# NewChip.net
KiCad netlist of a schematic drawn in Altium Designer
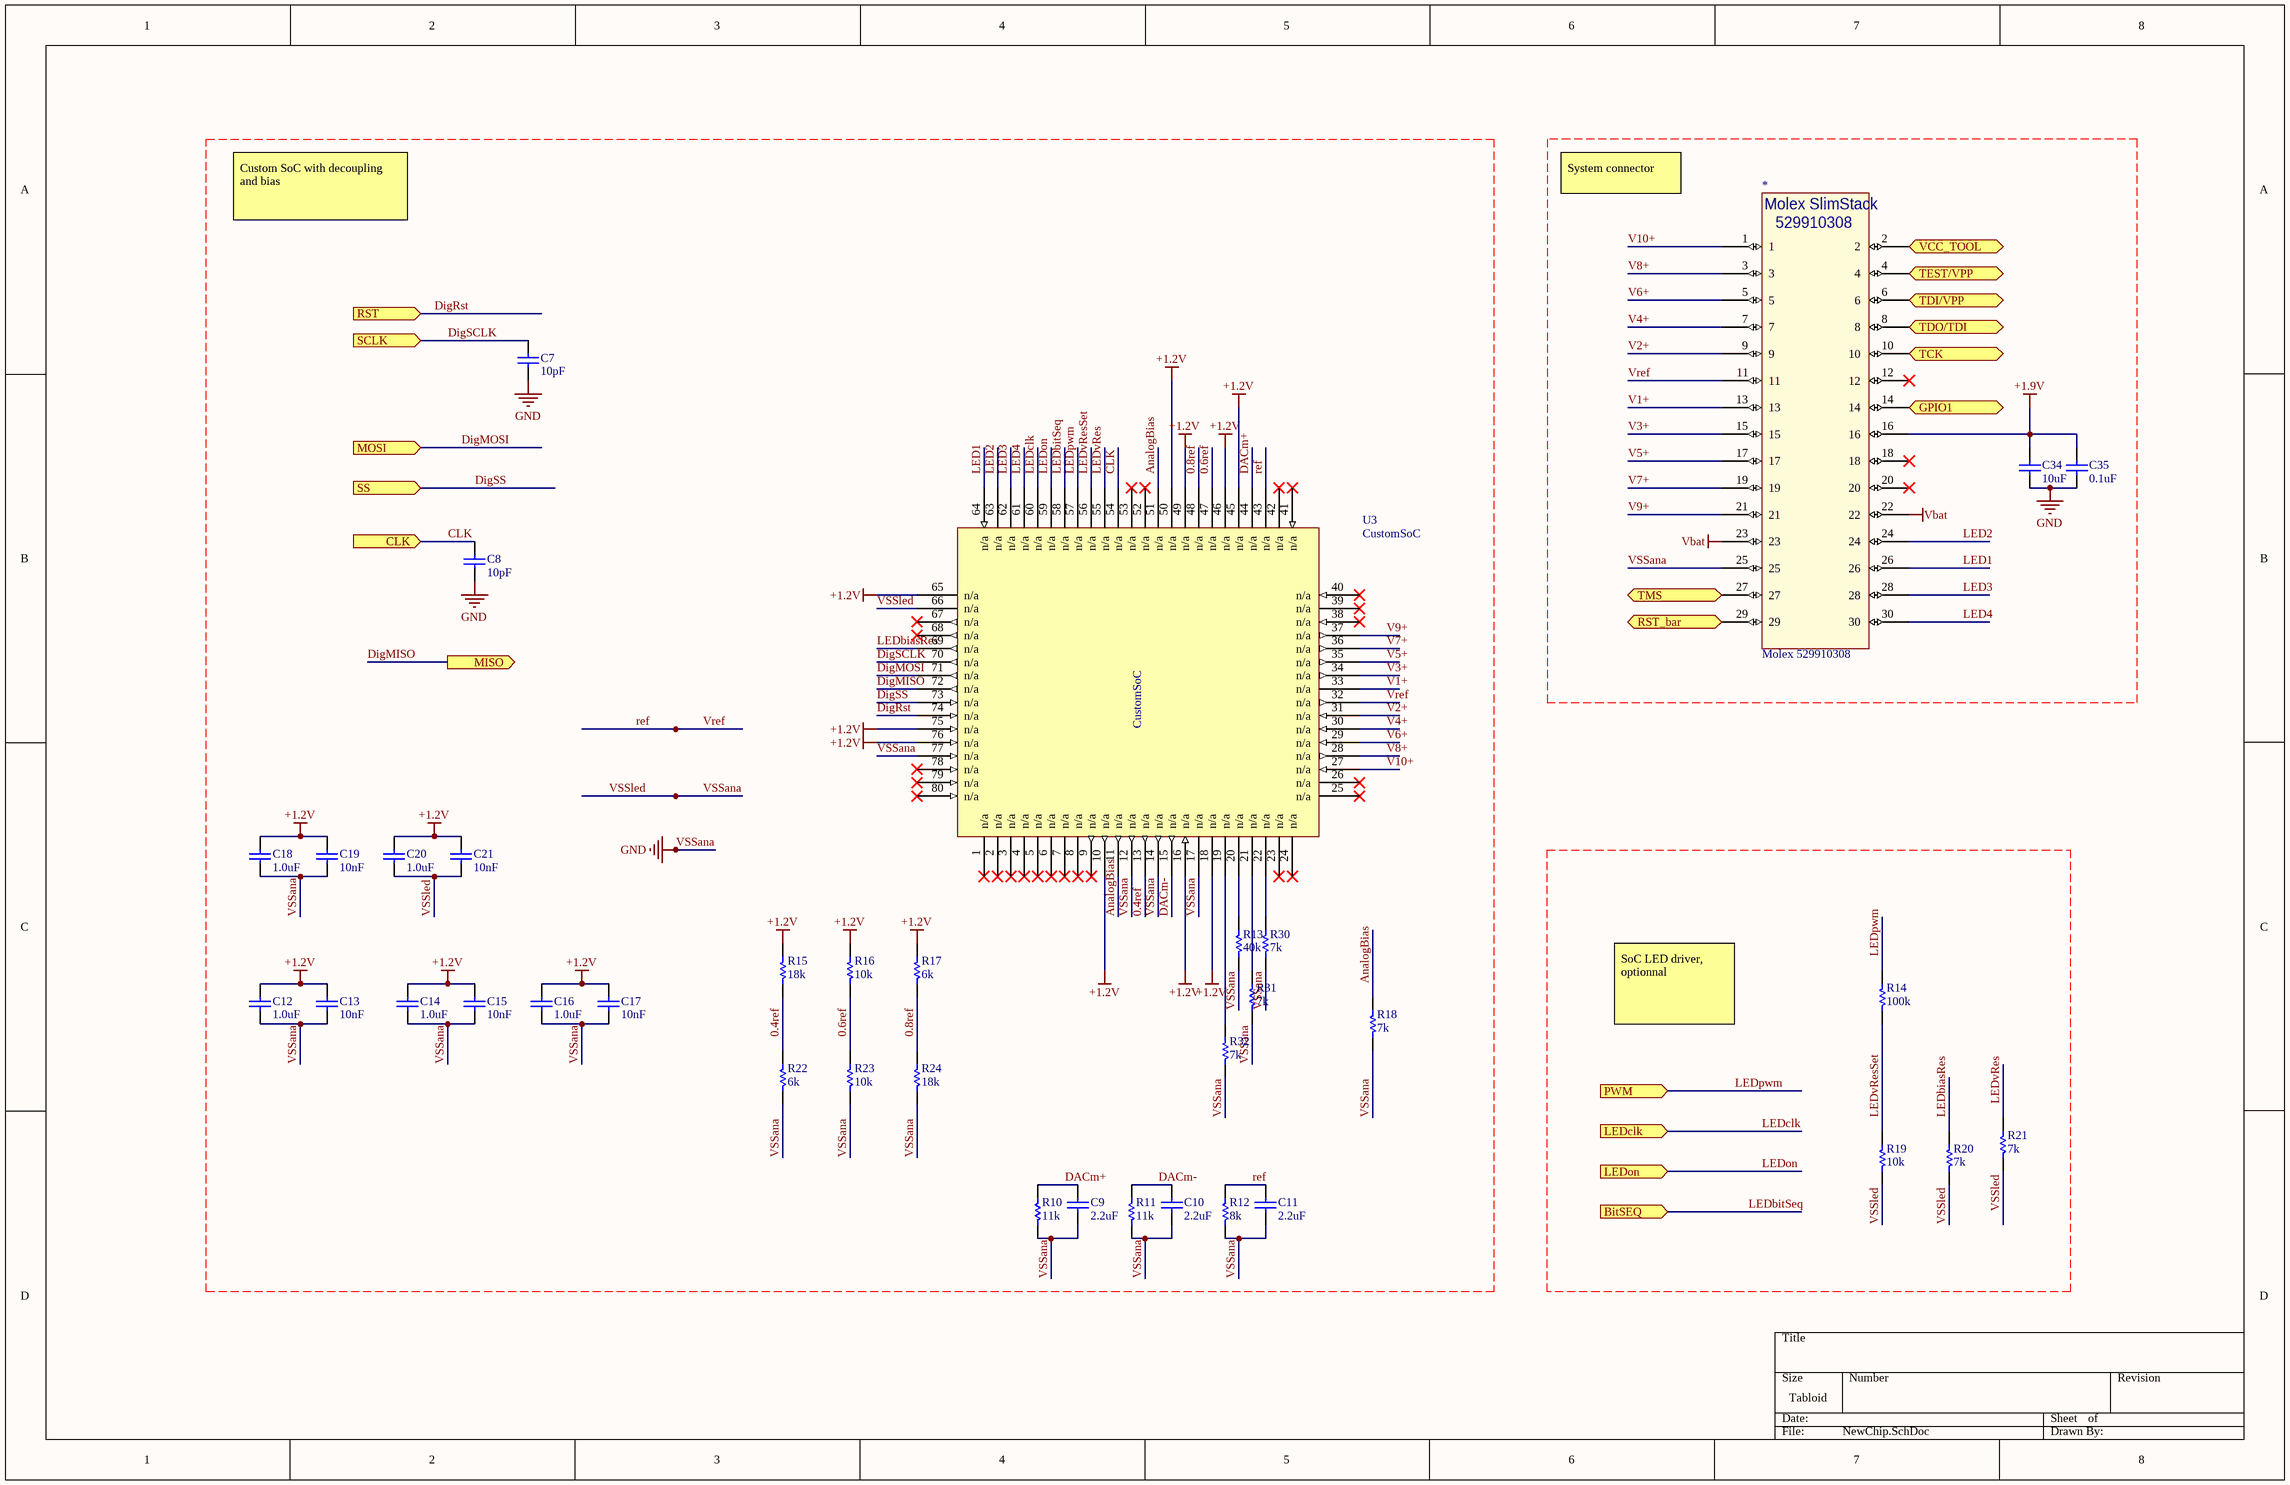
[diagram p0: NewChip.SchDoc]

(export (version "E")
  (design (tool "Eeschema 10.0.6"))
  (components
    (comp (ref "*")
      (value "Molex 529910308")
      (footprint "Molex 0529910308")
      (libsource (lib "headstage_parts") (part "Molex 529910308"))
    )
    (comp (ref "C7")
      (value "10pF")
      (footprint "0201_Custom")
      (description "Capacitor (Semiconductor SIM Model)")
      (fields (field (name "PUBLISHER") "Altium Limited"))
      (libsource (lib "Miscellaneous Devices") (part "Cap Semi"))
    )
    (comp (ref "C8")
      (value "10pF")
      (footprint "0201_Custom")
      (description "Capacitor (Semiconductor SIM Model)")
      (fields (field (name "PUBLISHER") "Altium Limited"))
      (libsource (lib "Miscellaneous Devices") (part "Cap Semi"))
    )
    (comp (ref "C9")
      (value "2.2uF")
      (footprint "0201_Custom")
      (description "Capacitor (Semiconductor SIM Model)")
      (fields (field (name "PUBLISHER") "Altium Limited"))
      (libsource (lib "Miscellaneous Devices") (part "Cap Semi"))
    )
    (comp (ref "C10")
      (value "2.2uF")
      (footprint "0201_Custom")
      (description "Capacitor (Semiconductor SIM Model)")
      (fields (field (name "PUBLISHER") "Altium Limited"))
      (libsource (lib "Miscellaneous Devices") (part "Cap Semi"))
    )
    (comp (ref "C11")
      (value "2.2uF")
      (footprint "0201_Custom")
      (description "Capacitor (Semiconductor SIM Model)")
      (fields (field (name "PUBLISHER") "Altium Limited"))
      (libsource (lib "Miscellaneous Devices") (part "Cap Semi"))
    )
    (comp (ref "C12")
      (value "1.0uF")
      (footprint "0201_Custom")
      (description "Capacitor (Semiconductor SIM Model)")
      (fields (field (name "PUBLISHER") "Altium Limited"))
      (libsource (lib "Miscellaneous Devices") (part "Cap Semi"))
    )
    (comp (ref "C13")
      (value "10nF")
      (footprint "0201_Custom")
      (description "Capacitor (Semiconductor SIM Model)")
      (fields (field (name "PUBLISHER") "Altium Limited"))
      (libsource (lib "Miscellaneous Devices") (part "Cap Semi"))
    )
    (comp (ref "C14")
      (value "1.0uF")
      (footprint "0201_Custom")
      (description "Capacitor (Semiconductor SIM Model)")
      (fields (field (name "PUBLISHER") "Altium Limited"))
      (libsource (lib "Miscellaneous Devices") (part "Cap Semi"))
    )
    (comp (ref "C15")
      (value "10nF")
      (footprint "0201_Custom")
      (description "Capacitor (Semiconductor SIM Model)")
      (fields (field (name "PUBLISHER") "Altium Limited"))
      (libsource (lib "Miscellaneous Devices") (part "Cap Semi"))
    )
    (comp (ref "C16")
      (value "1.0uF")
      (footprint "0201_Custom")
      (description "Capacitor (Semiconductor SIM Model)")
      (fields (field (name "PUBLISHER") "Altium Limited"))
      (libsource (lib "Miscellaneous Devices") (part "Cap Semi"))
    )
    (comp (ref "C17")
      (value "10nF")
      (footprint "0201_Custom")
      (description "Capacitor (Semiconductor SIM Model)")
      (fields (field (name "PUBLISHER") "Altium Limited"))
      (libsource (lib "Miscellaneous Devices") (part "Cap Semi"))
    )
    (comp (ref "C18")
      (value "1.0uF")
      (footprint "0201_Custom")
      (description "Capacitor (Semiconductor SIM Model)")
      (fields (field (name "PUBLISHER") "Altium Limited"))
      (libsource (lib "Miscellaneous Devices") (part "Cap Semi"))
    )
    (comp (ref "C19")
      (value "10nF")
      (footprint "0201_Custom")
      (description "Capacitor (Semiconductor SIM Model)")
      (fields (field (name "PUBLISHER") "Altium Limited"))
      (libsource (lib "Miscellaneous Devices") (part "Cap Semi"))
    )
    (comp (ref "C20")
      (value "1.0uF")
      (footprint "0201_Custom")
      (description "Capacitor (Semiconductor SIM Model)")
      (fields (field (name "PUBLISHER") "Altium Limited"))
      (libsource (lib "Miscellaneous Devices") (part "Cap Semi"))
    )
    (comp (ref "C21")
      (value "10nF")
      (footprint "0201_Custom")
      (description "Capacitor (Semiconductor SIM Model)")
      (fields (field (name "PUBLISHER") "Altium Limited"))
      (libsource (lib "Miscellaneous Devices") (part "Cap Semi"))
    )
    (comp (ref "C34")
      (value "10uF")
      (footprint "0402")
      (description "Capacitor (Semiconductor SIM Model)")
      (fields (field (name "PUBLISHER") "Altium Limited"))
      (libsource (lib "Miscellaneous Devices") (part "Cap Semi"))
    )
    (comp (ref "C35")
      (value "0.1uF")
      (footprint "0201_Custom")
      (description "Capacitor (Semiconductor SIM Model)")
      (fields (field (name "PUBLISHER") "Altium Limited"))
      (libsource (lib "Miscellaneous Devices") (part "Cap Semi"))
    )
    (comp (ref "R10")
      (value "11k")
      (footprint "0201_Custom")
      (description "Semiconductor Resistor")
      (fields (field (name "PUBLISHER") "Altium Limited"))
      (libsource (lib "Miscellaneous Devices") (part "Res Semi"))
    )
    (comp (ref "R11")
      (value "11k")
      (footprint "0201_Custom")
      (description "Semiconductor Resistor")
      (fields (field (name "PUBLISHER") "Altium Limited"))
      (libsource (lib "Miscellaneous Devices") (part "Res Semi"))
    )
    (comp (ref "R12")
      (value "8k")
      (footprint "0201_Custom")
      (description "Semiconductor Resistor")
      (fields (field (name "PUBLISHER") "Altium Limited"))
      (libsource (lib "Miscellaneous Devices") (part "Res Semi"))
    )
    (comp (ref "R13")
      (value "40k")
      (footprint "0201_Custom")
      (description "Semiconductor Resistor")
      (fields (field (name "PUBLISHER") "Altium Limited"))
      (libsource (lib "Miscellaneous Devices") (part "Res Semi"))
    )
    (comp (ref "R14")
      (value "100k")
      (footprint "0201_Custom")
      (description "Semiconductor Resistor")
      (fields (field (name "PUBLISHER") "Altium Limited"))
      (libsource (lib "Miscellaneous Devices") (part "Res Semi"))
    )
    (comp (ref "R15")
      (value "18k")
      (footprint "0201_Custom")
      (description "Semiconductor Resistor")
      (fields (field (name "PUBLISHER") "Altium Limited"))
      (libsource (lib "Miscellaneous Devices") (part "Res Semi"))
    )
    (comp (ref "R16")
      (value "10k")
      (footprint "0201_Custom")
      (description "Semiconductor Resistor")
      (fields (field (name "PUBLISHER") "Altium Limited"))
      (libsource (lib "Miscellaneous Devices") (part "Res Semi"))
    )
    (comp (ref "R17")
      (value "6k")
      (footprint "0201_Custom")
      (description "Semiconductor Resistor")
      (fields (field (name "PUBLISHER") "Altium Limited"))
      (libsource (lib "Miscellaneous Devices") (part "Res Semi"))
    )
    (comp (ref "R18")
      (value "7k")
      (footprint "0201_Custom")
      (description "Semiconductor Resistor")
      (fields (field (name "PUBLISHER") "Altium Limited"))
      (libsource (lib "Miscellaneous Devices") (part "Res Semi"))
    )
    (comp (ref "R19")
      (value "10k")
      (footprint "0201_Custom")
      (description "Semiconductor Resistor")
      (fields (field (name "PUBLISHER") "Altium Limited"))
      (libsource (lib "Miscellaneous Devices") (part "Res Semi"))
    )
    (comp (ref "R20")
      (value "7k")
      (footprint "0201_Custom")
      (description "Semiconductor Resistor")
      (fields (field (name "PUBLISHER") "Altium Limited"))
      (libsource (lib "Miscellaneous Devices") (part "Res Semi"))
    )
    (comp (ref "R21")
      (value "7k")
      (footprint "0201_Custom")
      (description "Semiconductor Resistor")
      (fields (field (name "PUBLISHER") "Altium Limited"))
      (libsource (lib "Miscellaneous Devices") (part "Res Semi"))
    )
    (comp (ref "R22")
      (value "6k")
      (footprint "0201_Custom")
      (description "Semiconductor Resistor")
      (fields (field (name "PUBLISHER") "Altium Limited"))
      (libsource (lib "Miscellaneous Devices") (part "Res Semi"))
    )
    (comp (ref "R23")
      (value "10k")
      (footprint "0201_Custom")
      (description "Semiconductor Resistor")
      (fields (field (name "PUBLISHER") "Altium Limited"))
      (libsource (lib "Miscellaneous Devices") (part "Res Semi"))
    )
    (comp (ref "R24")
      (value "18k")
      (footprint "0201_Custom")
      (description "Semiconductor Resistor")
      (fields (field (name "PUBLISHER") "Altium Limited"))
      (libsource (lib "Miscellaneous Devices") (part "Res Semi"))
    )
    (comp (ref "R30")
      (value "7k")
      (footprint "0201_Custom")
      (description "Semiconductor Resistor")
      (fields (field (name "PUBLISHER") "Altium Limited"))
      (libsource (lib "Miscellaneous Devices") (part "Res Semi"))
    )
    (comp (ref "R31")
      (value "7k")
      (footprint "0201_Custom")
      (description "Semiconductor Resistor")
      (fields (field (name "PUBLISHER") "Altium Limited"))
      (libsource (lib "Miscellaneous Devices") (part "Res Semi"))
    )
    (comp (ref "R32")
      (value "7k")
      (footprint "0201_Custom")
      (description "Semiconductor Resistor")
      (fields (field (name "PUBLISHER") "Altium Limited"))
      (libsource (lib "Miscellaneous Devices") (part "Res Semi"))
    )
    (comp (ref "U3")
      (value "CustomSoC")
      (footprint "CustomSoC")
      (libsource (lib "CustomLib") (part "CustomSoC"))
    )
  )
  (nets
    (net (code "1") (name "+1.2V") (class "Default")
      (node (ref "C12") (pin "1") (pinfunction "1_1") (pintype "passive"))
      (node (ref "C13") (pin "1") (pinfunction "1_1") (pintype "passive"))
      (node (ref "C14") (pin "1") (pinfunction "1_1") (pintype "passive"))
      (node (ref "C15") (pin "1") (pinfunction "1_1") (pintype "passive"))
      (node (ref "C16") (pin "1") (pinfunction "1_1") (pintype "passive"))
      (node (ref "C17") (pin "1") (pinfunction "1_1") (pintype "passive"))
      (node (ref "C18") (pin "1") (pinfunction "1_1") (pintype "passive"))
      (node (ref "C19") (pin "1") (pinfunction "1_1") (pintype "passive"))
      (node (ref "C20") (pin "1") (pinfunction "1_1") (pintype "passive"))
      (node (ref "C21") (pin "1") (pinfunction "1_1") (pintype "passive"))
      (node (ref "R15") (pin "1") (pinfunction "1_1") (pintype "passive"))
      (node (ref "R16") (pin "1") (pinfunction "1_1") (pintype "passive"))
      (node (ref "R17") (pin "1") (pinfunction "1_1") (pintype "passive"))
      (node (ref "U3") (pin "10") (pinfunction "n/a_10") (pintype "output"))
      (node (ref "U3") (pin "16") (pinfunction "n/a_16") (pintype "input"))
      (node (ref "U3") (pin "18") (pinfunction "n/a_18") (pintype "passive"))
      (node (ref "U3") (pin "45") (pinfunction "n/a_45") (pintype "passive"))
      (node (ref "U3") (pin "46") (pinfunction "n/a_46") (pintype "passive"))
      (node (ref "U3") (pin "49") (pinfunction "n/a_49") (pintype "passive"))
      (node (ref "U3") (pin "50") (pinfunction "n/a_50") (pintype "passive"))
      (node (ref "U3") (pin "65") (pinfunction "n/a_65") (pintype "power_in"))
      (node (ref "U3") (pin "75") (pinfunction "n/a_75") (pintype "input"))
      (node (ref "U3") (pin "76") (pinfunction "n/a_76") (pintype "input"))
    )
    (net (code "2") (name "+1.9V") (class "Default")
      (node (ref "*") (pin "16") (pinfunction "16_16") (pintype "bidirectional"))
      (node (ref "C34") (pin "2") (pinfunction "2_2") (pintype "passive"))
      (node (ref "C35") (pin "2") (pinfunction "2_2") (pintype "passive"))
    )
    (net (code "3") (name "/0.4ref") (class "Default")
      (node (ref "R15") (pin "2") (pinfunction "2_2") (pintype "passive"))
      (node (ref "R22") (pin "1") (pinfunction "1_1") (pintype "passive"))
      (node (ref "U3") (pin "13") (pinfunction "n/a_13") (pintype "output"))
    )
    (net (code "4") (name "/0.6ref") (class "Default")
      (node (ref "R16") (pin "2") (pinfunction "2_2") (pintype "passive"))
      (node (ref "R23") (pin "1") (pinfunction "1_1") (pintype "passive"))
      (node (ref "U3") (pin "47") (pinfunction "n/a_47") (pintype "passive"))
    )
    (net (code "5") (name "/0.8ref") (class "Default")
      (node (ref "R17") (pin "2") (pinfunction "2_2") (pintype "passive"))
      (node (ref "R24") (pin "1") (pinfunction "1_1") (pintype "passive"))
      (node (ref "U3") (pin "48") (pinfunction "n/a_48") (pintype "passive"))
    )
    (net (code "6") (name "/AnalogBias") (class "Default")
      (node (ref "R18") (pin "1") (pinfunction "1_1") (pintype "passive"))
      (node (ref "U3") (pin "11") (pinfunction "n/a_11") (pintype "output"))
      (node (ref "U3") (pin "51") (pinfunction "n/a_51") (pintype "passive"))
    )
    (net (code "7") (name "/CLK") (class "Default")
      (node (ref "C8") (pin "1") (pinfunction "1_1") (pintype "passive"))
      (node (ref "U3") (pin "54") (pinfunction "n/a_54") (pintype "passive"))
    )
    (net (code "8") (name "/DACm+") (class "Default")
      (node (ref "C9") (pin "1") (pinfunction "1_1") (pintype "passive"))
      (node (ref "R10") (pin "1") (pinfunction "1_1") (pintype "passive"))
      (node (ref "U3") (pin "44") (pinfunction "n/a_44") (pintype "passive"))
    )
    (net (code "9") (name "/DACm-") (class "Default")
      (node (ref "C10") (pin "1") (pinfunction "1_1") (pintype "passive"))
      (node (ref "R11") (pin "1") (pinfunction "1_1") (pintype "passive"))
      (node (ref "U3") (pin "15") (pinfunction "n/a_15") (pintype "output"))
    )
    (net (code "10") (name "/DigMISO") (class "Default")
      (node (ref "U3") (pin "72") (pinfunction "n/a_72") (pintype "output"))
    )
    (net (code "11") (name "/DigMOSI") (class "Default")
      (node (ref "U3") (pin "71") (pinfunction "n/a_71") (pintype "output"))
    )
    (net (code "12") (name "/DigRst") (class "Default")
      (node (ref "U3") (pin "74") (pinfunction "n/a_74") (pintype "input"))
    )
    (net (code "13") (name "/DigSCLK") (class "Default")
      (node (ref "C7") (pin "1") (pinfunction "1_1") (pintype "passive"))
      (node (ref "U3") (pin "70") (pinfunction "n/a_70") (pintype "output"))
    )
    (net (code "14") (name "/DigSS") (class "Default")
      (node (ref "U3") (pin "73") (pinfunction "n/a_73") (pintype "input"))
    )
    (net (code "15") (name "/GPIO1") (class "Default")
      (node (ref "*") (pin "14") (pinfunction "14_14") (pintype "bidirectional"))
    )
    (net (code "16") (name "/LED1") (class "Default")
      (node (ref "*") (pin "26") (pinfunction "26_26") (pintype "bidirectional"))
      (node (ref "U3") (pin "64") (pinfunction "n/a_64") (pintype "input"))
    )
    (net (code "17") (name "/LED2") (class "Default")
      (node (ref "*") (pin "24") (pinfunction "24_24") (pintype "bidirectional"))
      (node (ref "U3") (pin "63") (pinfunction "n/a_63") (pintype "passive"))
    )
    (net (code "18") (name "/LED3") (class "Default")
      (node (ref "*") (pin "28") (pinfunction "28_28") (pintype "bidirectional"))
      (node (ref "U3") (pin "62") (pinfunction "n/a_62") (pintype "passive"))
    )
    (net (code "19") (name "/LED4") (class "Default")
      (node (ref "*") (pin "30") (pinfunction "30_30") (pintype "bidirectional"))
      (node (ref "U3") (pin "61") (pinfunction "n/a_61") (pintype "passive"))
    )
    (net (code "20") (name "/LEDbiasRes") (class "Default")
      (node (ref "R20") (pin "1") (pinfunction "1_1") (pintype "passive"))
      (node (ref "U3") (pin "69") (pinfunction "n/a_69") (pintype "output"))
    )
    (net (code "21") (name "/LEDbitSeq") (class "Default")
      (node (ref "U3") (pin "58") (pinfunction "n/a_58") (pintype "passive"))
    )
    (net (code "22") (name "/LEDclk") (class "Default")
      (node (ref "U3") (pin "60") (pinfunction "n/a_60") (pintype "passive"))
    )
    (net (code "23") (name "/LEDon") (class "Default")
      (node (ref "U3") (pin "59") (pinfunction "n/a_59") (pintype "passive"))
    )
    (net (code "24") (name "/LEDpwm") (class "Default")
      (node (ref "R14") (pin "1") (pinfunction "1_1") (pintype "passive"))
      (node (ref "U3") (pin "57") (pinfunction "n/a_57") (pintype "passive"))
    )
    (net (code "25") (name "/LEDvRes") (class "Default")
      (node (ref "R21") (pin "1") (pinfunction "1_1") (pintype "passive"))
      (node (ref "U3") (pin "55") (pinfunction "n/a_55") (pintype "passive"))
    )
    (net (code "26") (name "/LEDvResSet") (class "Default")
      (node (ref "R14") (pin "2") (pinfunction "2_2") (pintype "passive"))
      (node (ref "R19") (pin "1") (pinfunction "1_1") (pintype "passive"))
      (node (ref "U3") (pin "56") (pinfunction "n/a_56") (pintype "passive"))
    )
    (net (code "27") (name "/RST_bar") (class "Default")
      (node (ref "*") (pin "29") (pinfunction "29_29") (pintype "bidirectional"))
    )
    (net (code "28") (name "/TCK") (class "Default")
      (node (ref "*") (pin "10") (pinfunction "10_10") (pintype "bidirectional"))
    )
    (net (code "29") (name "/TDI{slash}VPP") (class "Default")
      (node (ref "*") (pin "6") (pinfunction "6_6") (pintype "bidirectional"))
    )
    (net (code "30") (name "/TDO{slash}TDI") (class "Default")
      (node (ref "*") (pin "8") (pinfunction "8_8") (pintype "bidirectional"))
    )
    (net (code "31") (name "/TEST{slash}VPP") (class "Default")
      (node (ref "*") (pin "4") (pinfunction "4_4") (pintype "bidirectional"))
    )
    (net (code "32") (name "/TMS") (class "Default")
      (node (ref "*") (pin "27") (pinfunction "27_27") (pintype "bidirectional"))
    )
    (net (code "33") (name "/V1+") (class "Default")
      (node (ref "*") (pin "13") (pinfunction "13_13") (pintype "bidirectional"))
      (node (ref "U3") (pin "33") (pinfunction "n/a_33") (pintype "passive"))
    )
    (net (code "34") (name "/V2+") (class "Default")
      (node (ref "*") (pin "9") (pinfunction "9_9") (pintype "bidirectional"))
      (node (ref "U3") (pin "31") (pinfunction "n/a_31") (pintype "input"))
    )
    (net (code "35") (name "/V3+") (class "Default")
      (node (ref "*") (pin "15") (pinfunction "15_15") (pintype "bidirectional"))
      (node (ref "U3") (pin "34") (pinfunction "n/a_34") (pintype "output"))
    )
    (net (code "36") (name "/V4+") (class "Default")
      (node (ref "*") (pin "7") (pinfunction "7_7") (pintype "bidirectional"))
      (node (ref "U3") (pin "30") (pinfunction "n/a_30") (pintype "input"))
    )
    (net (code "37") (name "/V5+") (class "Default")
      (node (ref "*") (pin "17") (pinfunction "17_17") (pintype "bidirectional"))
      (node (ref "U3") (pin "35") (pinfunction "n/a_35") (pintype "output"))
    )
    (net (code "38") (name "/V6+") (class "Default")
      (node (ref "*") (pin "5") (pinfunction "5_5") (pintype "bidirectional"))
      (node (ref "U3") (pin "29") (pinfunction "n/a_29") (pintype "input"))
    )
    (net (code "39") (name "/V7+") (class "Default")
      (node (ref "*") (pin "19") (pinfunction "19_19") (pintype "bidirectional"))
      (node (ref "U3") (pin "36") (pinfunction "n/a_36") (pintype "output"))
    )
    (net (code "40") (name "/V8+") (class "Default")
      (node (ref "*") (pin "3") (pinfunction "3_3") (pintype "bidirectional"))
      (node (ref "U3") (pin "28") (pinfunction "n/a_28") (pintype "output"))
    )
    (net (code "41") (name "/V9+") (class "Default")
      (node (ref "*") (pin "21") (pinfunction "21_21") (pintype "bidirectional"))
      (node (ref "U3") (pin "37") (pinfunction "n/a_37") (pintype "output"))
    )
    (net (code "42") (name "/V10+") (class "Default")
      (node (ref "*") (pin "1") (pinfunction "1_1") (pintype "bidirectional"))
      (node (ref "U3") (pin "27") (pinfunction "n/a_27") (pintype "input"))
    )
    (net (code "43") (name "/VCC_TOOL") (class "Default")
      (node (ref "*") (pin "2") (pinfunction "2_2") (pintype "bidirectional"))
    )
    (net (code "44") (name "/Vref") (class "Default")
      (node (ref "*") (pin "11") (pinfunction "11_11") (pintype "bidirectional"))
      (node (ref "C11") (pin "1") (pinfunction "1_1") (pintype "passive"))
      (node (ref "R12") (pin "1") (pinfunction "1_1") (pintype "passive"))
      (node (ref "U3") (pin "32") (pinfunction "n/a_32") (pintype "output"))
      (node (ref "U3") (pin "43") (pinfunction "n/a_43") (pintype "passive"))
    )
    (net (code "45") (name "GND") (class "Default")
      (node (ref "*") (pin "25") (pinfunction "25_25") (pintype "bidirectional"))
      (node (ref "C10") (pin "2") (pinfunction "2_2") (pintype "passive"))
      (node (ref "C11") (pin "2") (pinfunction "2_2") (pintype "passive"))
      (node (ref "C12") (pin "2") (pinfunction "2_2") (pintype "passive"))
      (node (ref "C13") (pin "2") (pinfunction "2_2") (pintype "passive"))
      (node (ref "C14") (pin "2") (pinfunction "2_2") (pintype "passive"))
      (node (ref "C15") (pin "2") (pinfunction "2_2") (pintype "passive"))
      (node (ref "C16") (pin "2") (pinfunction "2_2") (pintype "passive"))
      (node (ref "C17") (pin "2") (pinfunction "2_2") (pintype "passive"))
      (node (ref "C18") (pin "2") (pinfunction "2_2") (pintype "passive"))
      (node (ref "C19") (pin "2") (pinfunction "2_2") (pintype "passive"))
      (node (ref "C20") (pin "2") (pinfunction "2_2") (pintype "passive"))
      (node (ref "C21") (pin "2") (pinfunction "2_2") (pintype "passive"))
      (node (ref "C34") (pin "1") (pinfunction "1_1") (pintype "passive"))
      (node (ref "C35") (pin "1") (pinfunction "1_1") (pintype "passive"))
      (node (ref "C7") (pin "2") (pinfunction "2_2") (pintype "passive"))
      (node (ref "C8") (pin "2") (pinfunction "2_2") (pintype "passive"))
      (node (ref "C9") (pin "2") (pinfunction "2_2") (pintype "passive"))
      (node (ref "R10") (pin "2") (pinfunction "2_2") (pintype "passive"))
      (node (ref "R11") (pin "2") (pinfunction "2_2") (pintype "passive"))
      (node (ref "R12") (pin "2") (pinfunction "2_2") (pintype "passive"))
      (node (ref "R13") (pin "2") (pinfunction "2_2") (pintype "passive"))
      (node (ref "R18") (pin "2") (pinfunction "2_2") (pintype "passive"))
      (node (ref "R19") (pin "2") (pinfunction "2_2") (pintype "passive"))
      (node (ref "R20") (pin "2") (pinfunction "2_2") (pintype "passive"))
      (node (ref "R21") (pin "2") (pinfunction "2_2") (pintype "passive"))
      (node (ref "R22") (pin "2") (pinfunction "2_2") (pintype "passive"))
      (node (ref "R23") (pin "2") (pinfunction "2_2") (pintype "passive"))
      (node (ref "R24") (pin "2") (pinfunction "2_2") (pintype "passive"))
      (node (ref "R30") (pin "2") (pinfunction "2_2") (pintype "passive"))
      (node (ref "R31") (pin "2") (pinfunction "2_2") (pintype "passive"))
      (node (ref "R32") (pin "2") (pinfunction "2_2") (pintype "passive"))
      (node (ref "U3") (pin "12") (pinfunction "n/a_12") (pintype "output"))
      (node (ref "U3") (pin "14") (pinfunction "n/a_14") (pintype "output"))
      (node (ref "U3") (pin "17") (pinfunction "n/a_17") (pintype "passive"))
      (node (ref "U3") (pin "66") (pinfunction "n/a_66") (pintype "power_in"))
      (node (ref "U3") (pin "77") (pinfunction "n/a_77") (pintype "input"))
    )
    (net (code "46") (name "Net-(R13-Pad1)") (class "Default")
      (node (ref "R13") (pin "1") (pinfunction "1_1") (pintype "passive"))
      (node (ref "U3") (pin "20") (pinfunction "n/a_20") (pintype "passive"))
    )
    (net (code "47") (name "Net-(R30-Pad1)") (class "Default")
      (node (ref "R30") (pin "1") (pinfunction "1_1") (pintype "passive"))
      (node (ref "U3") (pin "22") (pinfunction "n/a_22") (pintype "passive"))
    )
    (net (code "48") (name "Net-(R31-Pad1)") (class "Default")
      (node (ref "R31") (pin "1") (pinfunction "1_1") (pintype "passive"))
      (node (ref "U3") (pin "21") (pinfunction "n/a_21") (pintype "passive"))
    )
    (net (code "49") (name "Net-(R32-Pad1)") (class "Default")
      (node (ref "R32") (pin "1") (pinfunction "1_1") (pintype "passive"))
      (node (ref "U3") (pin "19") (pinfunction "n/a_19") (pintype "passive"))
    )
    (net (code "50") (name "Vbat") (class "Default")
      (node (ref "*") (pin "22") (pinfunction "22_22") (pintype "bidirectional"))
      (node (ref "*") (pin "23") (pinfunction "23_23") (pintype "bidirectional"))
    )
    (net (code "51") (name "unconnected-(*-Pad12)") (class "Default")
      (node (ref "*") (pin "12") (pinfunction "12_12") (pintype "bidirectional+no_connect"))
    )
    (net (code "52") (name "unconnected-(*-Pad18)") (class "Default")
      (node (ref "*") (pin "18") (pinfunction "18_18") (pintype "bidirectional+no_connect"))
    )
    (net (code "53") (name "unconnected-(*-Pad20)") (class "Default")
      (node (ref "*") (pin "20") (pinfunction "20_20") (pintype "bidirectional+no_connect"))
    )
    (net (code "54") (name "unconnected-(U3-n{slash}a-Pad1)") (class "Default")
      (node (ref "U3") (pin "1") (pinfunction "n/a_1") (pintype "passive+no_connect"))
    )
    (net (code "55") (name "unconnected-(U3-n{slash}a-Pad2)") (class "Default")
      (node (ref "U3") (pin "2") (pinfunction "n/a_2") (pintype "passive+no_connect"))
    )
    (net (code "56") (name "unconnected-(U3-n{slash}a-Pad3)") (class "Default")
      (node (ref "U3") (pin "3") (pinfunction "n/a_3") (pintype "passive+no_connect"))
    )
    (net (code "57") (name "unconnected-(U3-n{slash}a-Pad4)") (class "Default")
      (node (ref "U3") (pin "4") (pinfunction "n/a_4") (pintype "passive+no_connect"))
    )
    (net (code "58") (name "unconnected-(U3-n{slash}a-Pad5)") (class "Default")
      (node (ref "U3") (pin "5") (pinfunction "n/a_5") (pintype "passive+no_connect"))
    )
    (net (code "59") (name "unconnected-(U3-n{slash}a-Pad6)") (class "Default")
      (node (ref "U3") (pin "6") (pinfunction "n/a_6") (pintype "passive+no_connect"))
    )
    (net (code "60") (name "unconnected-(U3-n{slash}a-Pad7)") (class "Default")
      (node (ref "U3") (pin "7") (pinfunction "n/a_7") (pintype "passive+no_connect"))
    )
    (net (code "61") (name "unconnected-(U3-n{slash}a-Pad8)") (class "Default")
      (node (ref "U3") (pin "8") (pinfunction "n/a_8") (pintype "passive+no_connect"))
    )
    (net (code "62") (name "unconnected-(U3-n{slash}a-Pad9)") (class "Default")
      (node (ref "U3") (pin "9") (pinfunction "n/a_9") (pintype "output+no_connect"))
    )
    (net (code "63") (name "unconnected-(U3-n{slash}a-Pad23)") (class "Default")
      (node (ref "U3") (pin "23") (pinfunction "n/a_23") (pintype "passive+no_connect"))
    )
    (net (code "64") (name "unconnected-(U3-n{slash}a-Pad24)") (class "Default")
      (node (ref "U3") (pin "24") (pinfunction "n/a_24") (pintype "passive+no_connect"))
    )
    (net (code "65") (name "unconnected-(U3-n{slash}a-Pad25)") (class "Default")
      (node (ref "U3") (pin "25") (pinfunction "n/a_25") (pintype "power_in+no_connect"))
    )
    (net (code "66") (name "unconnected-(U3-n{slash}a-Pad26)") (class "Default")
      (node (ref "U3") (pin "26") (pinfunction "n/a_26") (pintype "power_in+no_connect"))
    )
    (net (code "67") (name "unconnected-(U3-n{slash}a-Pad38)") (class "Default")
      (node (ref "U3") (pin "38") (pinfunction "n/a_38") (pintype "input+no_connect"))
    )
    (net (code "68") (name "unconnected-(U3-n{slash}a-Pad39)") (class "Default")
      (node (ref "U3") (pin "39") (pinfunction "n/a_39") (pintype "power_in+no_connect"))
    )
    (net (code "69") (name "unconnected-(U3-n{slash}a-Pad40)") (class "Default")
      (node (ref "U3") (pin "40") (pinfunction "n/a_40") (pintype "input+no_connect"))
    )
    (net (code "70") (name "unconnected-(U3-n{slash}a-Pad41)") (class "Default")
      (node (ref "U3") (pin "41") (pinfunction "n/a_41") (pintype "input+no_connect"))
    )
    (net (code "71") (name "unconnected-(U3-n{slash}a-Pad42)") (class "Default")
      (node (ref "U3") (pin "42") (pinfunction "n/a_42") (pintype "passive+no_connect"))
    )
    (net (code "72") (name "unconnected-(U3-n{slash}a-Pad52)") (class "Default")
      (node (ref "U3") (pin "52") (pinfunction "n/a_52") (pintype "passive+no_connect"))
    )
    (net (code "73") (name "unconnected-(U3-n{slash}a-Pad53)") (class "Default")
      (node (ref "U3") (pin "53") (pinfunction "n/a_53") (pintype "passive+no_connect"))
    )
    (net (code "74") (name "unconnected-(U3-n{slash}a-Pad67)") (class "Default")
      (node (ref "U3") (pin "67") (pinfunction "n/a_67") (pintype "output+no_connect"))
    )
    (net (code "75") (name "unconnected-(U3-n{slash}a-Pad68)") (class "Default")
      (node (ref "U3") (pin "68") (pinfunction "n/a_68") (pintype "output+no_connect"))
    )
    (net (code "76") (name "unconnected-(U3-n{slash}a-Pad78)") (class "Default")
      (node (ref "U3") (pin "78") (pinfunction "n/a_78") (pintype "input+no_connect"))
    )
    (net (code "77") (name "unconnected-(U3-n{slash}a-Pad79)") (class "Default")
      (node (ref "U3") (pin "79") (pinfunction "n/a_79") (pintype "input+no_connect"))
    )
    (net (code "78") (name "unconnected-(U3-n{slash}a-Pad80)") (class "Default")
      (node (ref "U3") (pin "80") (pinfunction "n/a_80") (pintype "input+no_connect"))
    )
  )
)
